# stm32h750ibk6-sig.net
KiCad netlist of a schematic drawn in Altium Designer
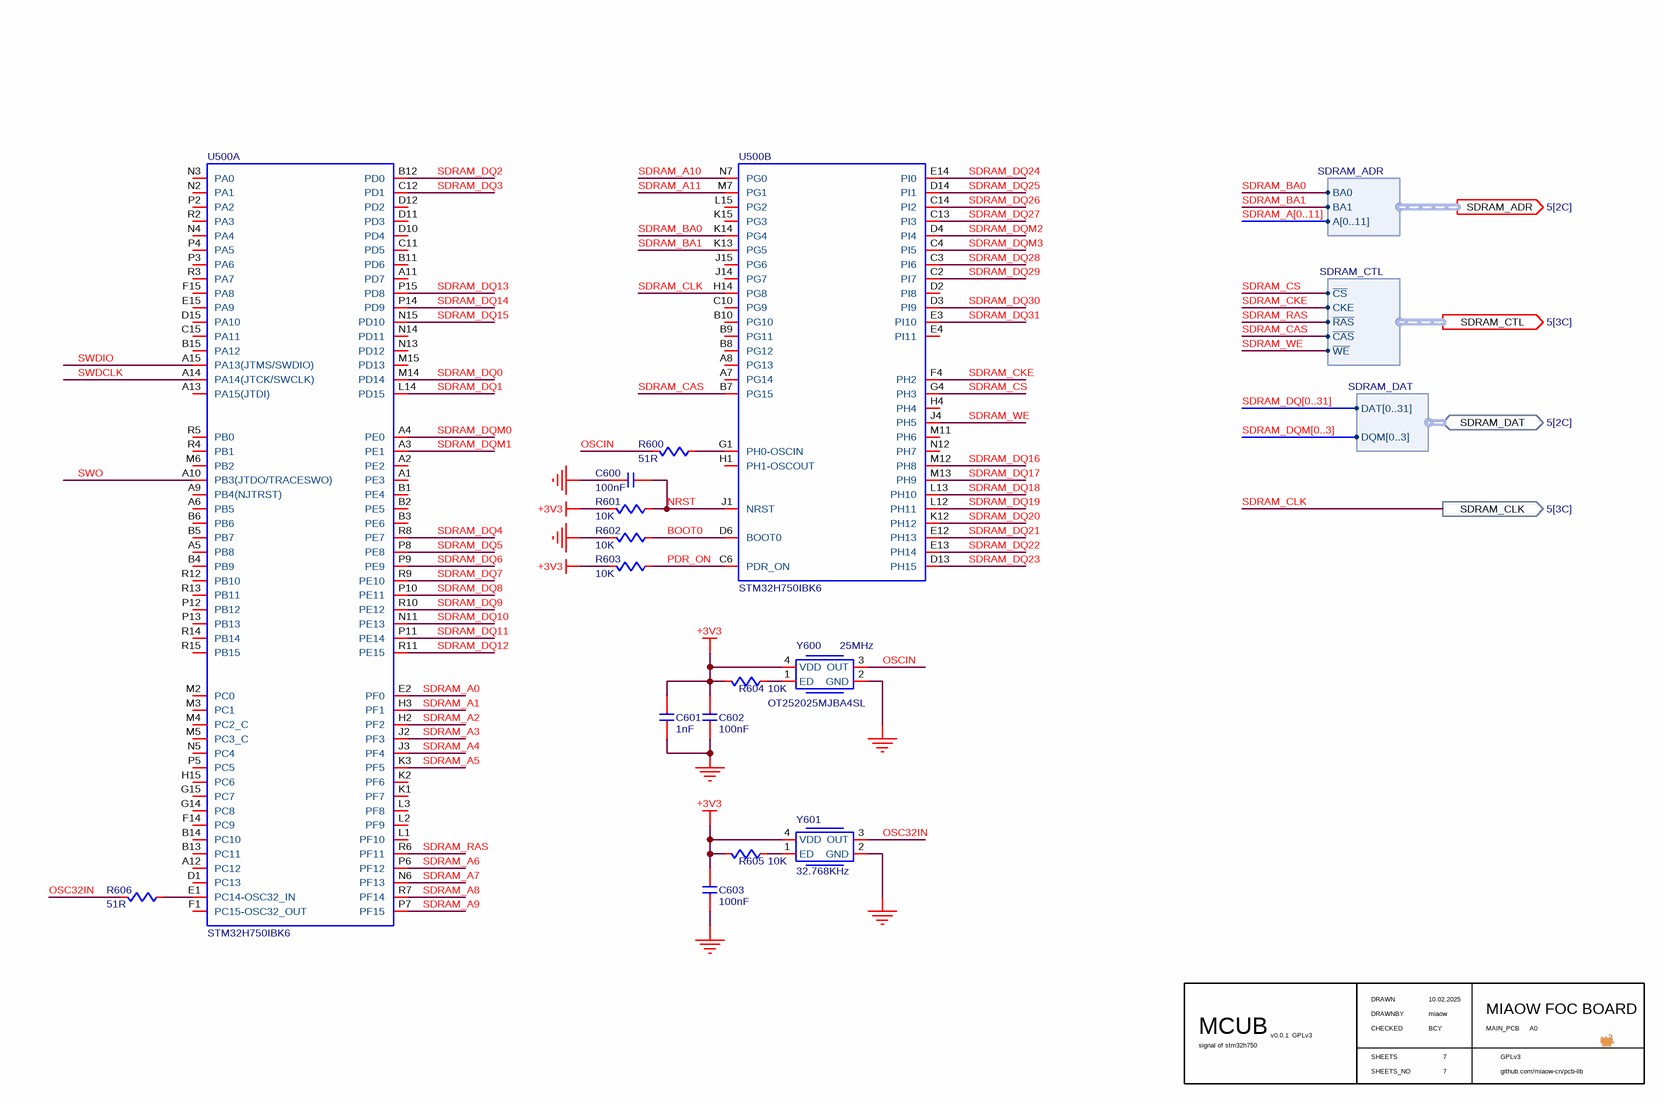
[diagram p0: stm32h750ibk6-sig.SchDoc]

(export (version "E")
  (design (tool "Eeschema 10.0.6"))
  (components
    (comp (ref "C600")
      (value "100nF")
      (footprint "mw:C0402")
      (fields (field (name "VOLTAGE") "25V") (field (name "Comment") "C-NOMO"))
      (libsource (lib "mw") (part "C-NOMO"))
    )
    (comp (ref "C601")
      (value "1nF")
      (footprint "mw:C0402")
      (fields (field (name "VOLTAGE") "25V") (field (name "Comment") "C-NOMO"))
      (libsource (lib "mw") (part "C-NOMO"))
    )
    (comp (ref "C602")
      (value "100nF")
      (footprint "mw:C0402")
      (fields (field (name "VOLTAGE") "25V") (field (name "Comment") "C-NOMO"))
      (libsource (lib "mw") (part "C-NOMO"))
    )
    (comp (ref "C603")
      (value "100nF")
      (footprint "mw:C0402")
      (fields (field (name "VOLTAGE") "25V") (field (name "Comment") "C-NOMO"))
      (libsource (lib "mw") (part "C-NOMO"))
    )
    (comp (ref "R600")
      (value "51R")
      (footprint "mw:R0402")
      (fields (field (name "Comment") "R"))
      (libsource (lib "mw") (part "R"))
    )
    (comp (ref "R601")
      (value "10K")
      (footprint "mw:R0402")
      (fields (field (name "Comment") "R"))
      (libsource (lib "mw") (part "R"))
    )
    (comp (ref "R602")
      (value "10K")
      (footprint "mw:R0402")
      (fields (field (name "Comment") "R"))
      (libsource (lib "mw") (part "R"))
    )
    (comp (ref "R603")
      (value "10K")
      (footprint "mw:R0402")
      (fields (field (name "Comment") "R"))
      (libsource (lib "mw") (part "R"))
    )
    (comp (ref "R604")
      (value "10K")
      (footprint "mw:R0402")
      (fields (field (name "Comment") "R"))
      (libsource (lib "mw") (part "R"))
    )
    (comp (ref "R605")
      (value "10K")
      (footprint "mw:R0402")
      (fields (field (name "Comment") "R"))
      (libsource (lib "mw") (part "R"))
    )
    (comp (ref "R606")
      (value "51R")
      (footprint "mw:R0402")
      (fields (field (name "Comment") "R"))
      (libsource (lib "mw") (part "R"))
    )
    (comp (ref "U500")
      (value "STM32H750IBK6")
      (footprint "mw:STM32H750IBK6")
      (libsource (lib "mw") (part "STM32H750IBK6"))
    )
    (comp (ref "Y600")
      (value "OT252025MJBA4SL")
      (footprint "mw:OT252025MJBA4SL")
      (fields (field (name "ALTIUM_VALUE") "25MHz"))
      (libsource (lib "mw") (part "OT252025MJBA4SL"))
    )
    (comp (ref "Y601")
      (value "32.768KHz")
      (footprint "mw:OK252032768KJBA4SL")
      (fields (field (name "Comment") "OK252032768KJBA4SL"))
      (libsource (lib "mw") (part "OK252032768KJBA4SL"))
    )
  )
  (nets
    (net (code "4") (name "+3V3") (class "Default")
      (node (ref "C601") (pin "1") (pinfunction "1_1") (pintype "passive"))
      (node (ref "C602") (pin "1") (pinfunction "1_1") (pintype "passive"))
      (node (ref "C603") (pin "1") (pinfunction "1_1") (pintype "passive"))
      (node (ref "R601") (pin "1") (pinfunction "1_1") (pintype "passive"))
      (node (ref "R603") (pin "1") (pinfunction "1_1") (pintype "passive"))
      (node (ref "R604") (pin "1") (pinfunction "1_1") (pintype "passive"))
      (node (ref "R605") (pin "1") (pinfunction "1_1") (pintype "passive"))
      (node (ref "Y600") (pin "4") (pinfunction "VDD_4") (pintype "passive"))
      (node (ref "Y601") (pin "4") (pinfunction "VDD_4") (pintype "passive"))
    )
    (net (code "5") (name "/BOOT0") (class "Default")
      (node (ref "R602") (pin "2") (pinfunction "2_2") (pintype "passive"))
      (node (ref "U500") (pin "D6") (pinfunction "BOOT0_D6") (pintype "passive"))
    )
    (net (code "6") (name "/NRST") (class "Default")
      (node (ref "C600") (pin "1") (pinfunction "1_1") (pintype "passive"))
      (node (ref "R601") (pin "2") (pinfunction "2_2") (pintype "passive"))
      (node (ref "U500") (pin "J1") (pinfunction "NRST_J1") (pintype "passive"))
    )
    (net (code "7") (name "/OSC32IN") (class "Default")
      (node (ref "R606") (pin "1") (pinfunction "1_1") (pintype "passive"))
      (node (ref "Y601") (pin "3") (pinfunction "OUT_3") (pintype "passive"))
    )
    (net (code "8") (name "/OSCIN") (class "Default")
      (node (ref "R600") (pin "1") (pinfunction "1_1") (pintype "passive"))
      (node (ref "Y600") (pin "3") (pinfunction "OUT_3") (pintype "passive"))
    )
    (net (code "9") (name "/PDR_ON") (class "Default")
      (node (ref "R603") (pin "2") (pinfunction "2_2") (pintype "passive"))
      (node (ref "U500") (pin "C6") (pinfunction "PDR_ON_C6") (pintype "passive"))
    )
    (net (code "10") (name "/SDRAM_A0") (class "Default")
      (node (ref "U500") (pin "E2") (pinfunction "PF0_E2") (pintype "passive"))
    )
    (net (code "11") (name "/SDRAM_A1") (class "Default")
      (node (ref "U500") (pin "H3") (pinfunction "PF1_H3") (pintype "passive"))
    )
    (net (code "12") (name "/SDRAM_A2") (class "Default")
      (node (ref "U500") (pin "H2") (pinfunction "PF2_H2") (pintype "passive"))
    )
    (net (code "13") (name "/SDRAM_A3") (class "Default")
      (node (ref "U500") (pin "J2") (pinfunction "PF3_J2") (pintype "passive"))
    )
    (net (code "14") (name "/SDRAM_A4") (class "Default")
      (node (ref "U500") (pin "J3") (pinfunction "PF4_J3") (pintype "passive"))
    )
    (net (code "15") (name "/SDRAM_A5") (class "Default")
      (node (ref "U500") (pin "K3") (pinfunction "PF5_K3") (pintype "passive"))
    )
    (net (code "16") (name "/SDRAM_A6") (class "Default")
      (node (ref "U500") (pin "P6") (pinfunction "PF12_P6") (pintype "passive"))
    )
    (net (code "17") (name "/SDRAM_A7") (class "Default")
      (node (ref "U500") (pin "N6") (pinfunction "PF13_N6") (pintype "passive"))
    )
    (net (code "18") (name "/SDRAM_A8") (class "Default")
      (node (ref "U500") (pin "R7") (pinfunction "PF14_R7") (pintype "passive"))
    )
    (net (code "19") (name "/SDRAM_A9") (class "Default")
      (node (ref "U500") (pin "P7") (pinfunction "PF15_P7") (pintype "passive"))
    )
    (net (code "20") (name "/SDRAM_A10") (class "Default")
      (node (ref "U500") (pin "N7") (pinfunction "PG0_N7") (pintype "passive"))
    )
    (net (code "21") (name "/SDRAM_A11") (class "Default")
      (node (ref "U500") (pin "M7") (pinfunction "PG1_M7") (pintype "passive"))
    )
    (net (code "23") (name "/SDRAM_BA0") (class "Default")
      (node (ref "U500") (pin "K14") (pinfunction "PG4_K14") (pintype "passive"))
    )
    (net (code "24") (name "/SDRAM_BA1") (class "Default")
      (node (ref "U500") (pin "K13") (pinfunction "PG5_K13") (pintype "passive"))
    )
    (net (code "25") (name "/SDRAM_CAS") (class "Default")
      (node (ref "U500") (pin "B7") (pinfunction "PG15_B7") (pintype "passive"))
    )
    (net (code "26") (name "/SDRAM_CKE") (class "Default")
      (node (ref "U500") (pin "F4") (pinfunction "PH2_F4") (pintype "passive"))
    )
    (net (code "27") (name "/SDRAM_CLK") (class "Default")
      (node (ref "U500") (pin "H14") (pinfunction "PG8_H14") (pintype "passive"))
    )
    (net (code "28") (name "/SDRAM_CS") (class "Default")
      (node (ref "U500") (pin "G4") (pinfunction "PH3_G4") (pintype "passive"))
    )
    (net (code "30") (name "/SDRAM_DQ0") (class "Default")
      (node (ref "U500") (pin "M14") (pinfunction "PD14_M14") (pintype "passive"))
    )
    (net (code "31") (name "/SDRAM_DQ1") (class "Default")
      (node (ref "U500") (pin "L14") (pinfunction "PD15_L14") (pintype "passive"))
    )
    (net (code "32") (name "/SDRAM_DQ2") (class "Default")
      (node (ref "U500") (pin "B12") (pinfunction "PD0_B12") (pintype "passive"))
    )
    (net (code "33") (name "/SDRAM_DQ3") (class "Default")
      (node (ref "U500") (pin "C12") (pinfunction "PD1_C12") (pintype "passive"))
    )
    (net (code "34") (name "/SDRAM_DQ4") (class "Default")
      (node (ref "U500") (pin "R8") (pinfunction "PE7_R8") (pintype "passive"))
    )
    (net (code "35") (name "/SDRAM_DQ5") (class "Default")
      (node (ref "U500") (pin "P8") (pinfunction "PE8_P8") (pintype "passive"))
    )
    (net (code "36") (name "/SDRAM_DQ6") (class "Default")
      (node (ref "U500") (pin "P9") (pinfunction "PE9_P9") (pintype "passive"))
    )
    (net (code "37") (name "/SDRAM_DQ7") (class "Default")
      (node (ref "U500") (pin "R9") (pinfunction "PE10_R9") (pintype "passive"))
    )
    (net (code "38") (name "/SDRAM_DQ8") (class "Default")
      (node (ref "U500") (pin "P10") (pinfunction "PE11_P10") (pintype "passive"))
    )
    (net (code "39") (name "/SDRAM_DQ9") (class "Default")
      (node (ref "U500") (pin "R10") (pinfunction "PE12_R10") (pintype "passive"))
    )
    (net (code "40") (name "/SDRAM_DQ10") (class "Default")
      (node (ref "U500") (pin "N11") (pinfunction "PE13_N11") (pintype "passive"))
    )
    (net (code "41") (name "/SDRAM_DQ11") (class "Default")
      (node (ref "U500") (pin "P11") (pinfunction "PE14_P11") (pintype "passive"))
    )
    (net (code "42") (name "/SDRAM_DQ12") (class "Default")
      (node (ref "U500") (pin "R11") (pinfunction "PE15_R11") (pintype "passive"))
    )
    (net (code "43") (name "/SDRAM_DQ13") (class "Default")
      (node (ref "U500") (pin "P15") (pinfunction "PD8_P15") (pintype "passive"))
    )
    (net (code "44") (name "/SDRAM_DQ14") (class "Default")
      (node (ref "U500") (pin "P14") (pinfunction "PD9_P14") (pintype "passive"))
    )
    (net (code "45") (name "/SDRAM_DQ15") (class "Default")
      (node (ref "U500") (pin "N15") (pinfunction "PD10_N15") (pintype "passive"))
    )
    (net (code "46") (name "/SDRAM_DQ16") (class "Default")
      (node (ref "U500") (pin "M12") (pinfunction "PH8_M12") (pintype "passive"))
    )
    (net (code "47") (name "/SDRAM_DQ17") (class "Default")
      (node (ref "U500") (pin "M13") (pinfunction "PH9_M13") (pintype "passive"))
    )
    (net (code "48") (name "/SDRAM_DQ18") (class "Default")
      (node (ref "U500") (pin "L13") (pinfunction "PH10_L13") (pintype "passive"))
    )
    (net (code "49") (name "/SDRAM_DQ19") (class "Default")
      (node (ref "U500") (pin "L12") (pinfunction "PH11_L12") (pintype "passive"))
    )
    (net (code "50") (name "/SDRAM_DQ20") (class "Default")
      (node (ref "U500") (pin "K12") (pinfunction "PH12_K12") (pintype "passive"))
    )
    (net (code "51") (name "/SDRAM_DQ21") (class "Default")
      (node (ref "U500") (pin "E12") (pinfunction "PH13_E12") (pintype "passive"))
    )
    (net (code "52") (name "/SDRAM_DQ22") (class "Default")
      (node (ref "U500") (pin "E13") (pinfunction "PH14_E13") (pintype "passive"))
    )
    (net (code "53") (name "/SDRAM_DQ23") (class "Default")
      (node (ref "U500") (pin "D13") (pinfunction "PH15_D13") (pintype "passive"))
    )
    (net (code "54") (name "/SDRAM_DQ24") (class "Default")
      (node (ref "U500") (pin "E14") (pinfunction "PI0_E14") (pintype "passive"))
    )
    (net (code "55") (name "/SDRAM_DQ25") (class "Default")
      (node (ref "U500") (pin "D14") (pinfunction "PI1_D14") (pintype "passive"))
    )
    (net (code "56") (name "/SDRAM_DQ26") (class "Default")
      (node (ref "U500") (pin "C14") (pinfunction "PI2_C14") (pintype "passive"))
    )
    (net (code "57") (name "/SDRAM_DQ27") (class "Default")
      (node (ref "U500") (pin "C13") (pinfunction "PI3_C13") (pintype "passive"))
    )
    (net (code "58") (name "/SDRAM_DQ28") (class "Default")
      (node (ref "U500") (pin "C3") (pinfunction "PI6_C3") (pintype "passive"))
    )
    (net (code "59") (name "/SDRAM_DQ29") (class "Default")
      (node (ref "U500") (pin "C2") (pinfunction "PI7_C2") (pintype "passive"))
    )
    (net (code "60") (name "/SDRAM_DQ30") (class "Default")
      (node (ref "U500") (pin "D3") (pinfunction "PI9_D3") (pintype "passive"))
    )
    (net (code "61") (name "/SDRAM_DQ31") (class "Default")
      (node (ref "U500") (pin "E3") (pinfunction "PI10_E3") (pintype "passive"))
    )
    (net (code "62") (name "/SDRAM_DQM0") (class "Default")
      (node (ref "U500") (pin "A4") (pinfunction "PE0_A4") (pintype "passive"))
    )
    (net (code "63") (name "/SDRAM_DQM1") (class "Default")
      (node (ref "U500") (pin "A3") (pinfunction "PE1_A3") (pintype "passive"))
    )
    (net (code "64") (name "/SDRAM_DQM2") (class "Default")
      (node (ref "U500") (pin "D4") (pinfunction "PI4_D4") (pintype "passive"))
    )
    (net (code "65") (name "/SDRAM_DQM3") (class "Default")
      (node (ref "U500") (pin "C4") (pinfunction "PI5_C4") (pintype "passive"))
    )
    (net (code "67") (name "/SDRAM_RAS") (class "Default")
      (node (ref "U500") (pin "R6") (pinfunction "PF11_R6") (pintype "passive"))
    )
    (net (code "68") (name "/SDRAM_WE") (class "Default")
      (node (ref "U500") (pin "J4") (pinfunction "PH5_J4") (pintype "passive"))
    )
    (net (code "69") (name "/SWDCLK") (class "Default")
      (node (ref "U500") (pin "A14") (pinfunction "PA14(JTCK/SWCLK)_A14") (pintype "passive"))
    )
    (net (code "70") (name "/SWDIO") (class "Default")
      (node (ref "U500") (pin "A15") (pinfunction "PA13(JTMS/SWDIO)_A15") (pintype "passive"))
    )
    (net (code "71") (name "/SWO") (class "Default")
      (node (ref "U500") (pin "A10") (pinfunction "PB3(JTDO/TRACESWO)_A10") (pintype "passive"))
    )
    (net (code "75") (name "GND") (class "Default")
      (node (ref "C600") (pin "2") (pinfunction "2_2") (pintype "passive"))
      (node (ref "C601") (pin "2") (pinfunction "2_2") (pintype "passive"))
      (node (ref "C602") (pin "2") (pinfunction "2_2") (pintype "passive"))
      (node (ref "C603") (pin "2") (pinfunction "2_2") (pintype "passive"))
      (node (ref "R602") (pin "1") (pinfunction "1_1") (pintype "passive"))
      (node (ref "Y600") (pin "2") (pinfunction "GND_2") (pintype "passive"))
      (node (ref "Y601") (pin "2") (pinfunction "GND_2") (pintype "passive"))
    )
    (net (code "76") (name "Net-(U500A-PC14-OSC32_IN)") (class "Default")
      (node (ref "R606") (pin "2") (pinfunction "2_2") (pintype "passive"))
      (node (ref "U500") (pin "E1") (pinfunction "PC14-OSC32_IN_E1") (pintype "passive"))
    )
    (net (code "77") (name "Net-(U500B-PH0-OSCIN)") (class "Default")
      (node (ref "R600") (pin "2") (pinfunction "2_2") (pintype "passive"))
      (node (ref "U500") (pin "G1") (pinfunction "PH0-OSCIN_G1") (pintype "passive"))
    )
    (net (code "78") (name "Net-(Y600-ED)") (class "Default")
      (node (ref "R604") (pin "2") (pinfunction "2_2") (pintype "passive"))
      (node (ref "Y600") (pin "1") (pinfunction "ED_1") (pintype "passive"))
    )
    (net (code "79") (name "Net-(Y601-ED)") (class "Default")
      (node (ref "R605") (pin "2") (pinfunction "2_2") (pintype "passive"))
      (node (ref "Y601") (pin "1") (pinfunction "ED_1") (pintype "passive"))
    )
    (net (code "80") (name "unconnected-(U500A-PA0-PadN3)") (class "Default")
      (node (ref "U500") (pin "N3") (pinfunction "PA0_N3") (pintype "passive"))
    )
    (net (code "81") (name "unconnected-(U500A-PA1-PadN2)") (class "Default")
      (node (ref "U500") (pin "N2") (pinfunction "PA1_N2") (pintype "passive"))
    )
    (net (code "82") (name "unconnected-(U500A-PA2-PadP2)") (class "Default")
      (node (ref "U500") (pin "P2") (pinfunction "PA2_P2") (pintype "passive"))
    )
    (net (code "83") (name "unconnected-(U500A-PA3-PadR2)") (class "Default")
      (node (ref "U500") (pin "R2") (pinfunction "PA3_R2") (pintype "passive"))
    )
    (net (code "84") (name "unconnected-(U500A-PA4-PadN4)") (class "Default")
      (node (ref "U500") (pin "N4") (pinfunction "PA4_N4") (pintype "passive"))
    )
    (net (code "85") (name "unconnected-(U500A-PA5-PadP4)") (class "Default")
      (node (ref "U500") (pin "P4") (pinfunction "PA5_P4") (pintype "passive"))
    )
    (net (code "86") (name "unconnected-(U500A-PA6-PadP3)") (class "Default")
      (node (ref "U500") (pin "P3") (pinfunction "PA6_P3") (pintype "passive"))
    )
    (net (code "87") (name "unconnected-(U500A-PA7-PadR3)") (class "Default")
      (node (ref "U500") (pin "R3") (pinfunction "PA7_R3") (pintype "passive"))
    )
    (net (code "88") (name "unconnected-(U500A-PA8-PadF15)") (class "Default")
      (node (ref "U500") (pin "F15") (pinfunction "PA8_F15") (pintype "passive"))
    )
    (net (code "89") (name "unconnected-(U500A-PA9-PadE15)") (class "Default")
      (node (ref "U500") (pin "E15") (pinfunction "PA9_E15") (pintype "passive"))
    )
    (net (code "90") (name "unconnected-(U500A-PA10-PadD15)") (class "Default")
      (node (ref "U500") (pin "D15") (pinfunction "PA10_D15") (pintype "passive"))
    )
    (net (code "91") (name "unconnected-(U500A-PA11-PadC15)") (class "Default")
      (node (ref "U500") (pin "C15") (pinfunction "PA11_C15") (pintype "passive"))
    )
    (net (code "92") (name "unconnected-(U500A-PA12-PadB15)") (class "Default")
      (node (ref "U500") (pin "B15") (pinfunction "PA12_B15") (pintype "passive"))
    )
    (net (code "93") (name "unconnected-(U500A-PA15(JTDI)-PadA13)") (class "Default")
      (node (ref "U500") (pin "A13") (pinfunction "PA15(JTDI)_A13") (pintype "passive"))
    )
    (net (code "94") (name "unconnected-(U500A-PB0-PadR5)") (class "Default")
      (node (ref "U500") (pin "R5") (pinfunction "PB0_R5") (pintype "passive"))
    )
    (net (code "95") (name "unconnected-(U500A-PB1-PadR4)") (class "Default")
      (node (ref "U500") (pin "R4") (pinfunction "PB1_R4") (pintype "passive"))
    )
    (net (code "96") (name "unconnected-(U500A-PB2-PadM6)") (class "Default")
      (node (ref "U500") (pin "M6") (pinfunction "PB2_M6") (pintype "passive"))
    )
    (net (code "97") (name "unconnected-(U500A-PB4(NJTRST)-PadA9)") (class "Default")
      (node (ref "U500") (pin "A9") (pinfunction "PB4(NJTRST)_A9") (pintype "passive"))
    )
    (net (code "98") (name "unconnected-(U500A-PB5-PadA6)") (class "Default")
      (node (ref "U500") (pin "A6") (pinfunction "PB5_A6") (pintype "passive"))
    )
    (net (code "99") (name "unconnected-(U500A-PB6-PadB6)") (class "Default")
      (node (ref "U500") (pin "B6") (pinfunction "PB6_B6") (pintype "passive"))
    )
    (net (code "100") (name "unconnected-(U500A-PB7-PadB5)") (class "Default")
      (node (ref "U500") (pin "B5") (pinfunction "PB7_B5") (pintype "passive"))
    )
    (net (code "101") (name "unconnected-(U500A-PB8-PadA5)") (class "Default")
      (node (ref "U500") (pin "A5") (pinfunction "PB8_A5") (pintype "passive"))
    )
    (net (code "102") (name "unconnected-(U500A-PB9-PadB4)") (class "Default")
      (node (ref "U500") (pin "B4") (pinfunction "PB9_B4") (pintype "passive"))
    )
    (net (code "103") (name "unconnected-(U500A-PB10-PadR12)") (class "Default")
      (node (ref "U500") (pin "R12") (pinfunction "PB10_R12") (pintype "passive"))
    )
    (net (code "104") (name "unconnected-(U500A-PB11-PadR13)") (class "Default")
      (node (ref "U500") (pin "R13") (pinfunction "PB11_R13") (pintype "passive"))
    )
    (net (code "105") (name "unconnected-(U500A-PB12-PadP12)") (class "Default")
      (node (ref "U500") (pin "P12") (pinfunction "PB12_P12") (pintype "passive"))
    )
    (net (code "106") (name "unconnected-(U500A-PB13-PadP13)") (class "Default")
      (node (ref "U500") (pin "P13") (pinfunction "PB13_P13") (pintype "passive"))
    )
    (net (code "107") (name "unconnected-(U500A-PB14-PadR14)") (class "Default")
      (node (ref "U500") (pin "R14") (pinfunction "PB14_R14") (pintype "passive"))
    )
    (net (code "108") (name "unconnected-(U500A-PB15-PadR15)") (class "Default")
      (node (ref "U500") (pin "R15") (pinfunction "PB15_R15") (pintype "passive"))
    )
    (net (code "109") (name "unconnected-(U500A-PC0-PadM2)") (class "Default")
      (node (ref "U500") (pin "M2") (pinfunction "PC0_M2") (pintype "passive"))
    )
    (net (code "110") (name "unconnected-(U500A-PC1-PadM3)") (class "Default")
      (node (ref "U500") (pin "M3") (pinfunction "PC1_M3") (pintype "passive"))
    )
    (net (code "111") (name "unconnected-(U500A-PC2_C-PadM4)") (class "Default")
      (node (ref "U500") (pin "M4") (pinfunction "PC2_C_M4") (pintype "passive"))
    )
    (net (code "112") (name "unconnected-(U500A-PC3_C-PadM5)") (class "Default")
      (node (ref "U500") (pin "M5") (pinfunction "PC3_C_M5") (pintype "passive"))
    )
    (net (code "113") (name "unconnected-(U500A-PC4-PadN5)") (class "Default")
      (node (ref "U500") (pin "N5") (pinfunction "PC4_N5") (pintype "passive"))
    )
    (net (code "114") (name "unconnected-(U500A-PC5-PadP5)") (class "Default")
      (node (ref "U500") (pin "P5") (pinfunction "PC5_P5") (pintype "passive"))
    )
    (net (code "115") (name "unconnected-(U500A-PC6-PadH15)") (class "Default")
      (node (ref "U500") (pin "H15") (pinfunction "PC6_H15") (pintype "passive"))
    )
    (net (code "116") (name "unconnected-(U500A-PC7-PadG15)") (class "Default")
      (node (ref "U500") (pin "G15") (pinfunction "PC7_G15") (pintype "passive"))
    )
    (net (code "117") (name "unconnected-(U500A-PC8-PadG14)") (class "Default")
      (node (ref "U500") (pin "G14") (pinfunction "PC8_G14") (pintype "passive"))
    )
    (net (code "118") (name "unconnected-(U500A-PC9-PadF14)") (class "Default")
      (node (ref "U500") (pin "F14") (pinfunction "PC9_F14") (pintype "passive"))
    )
    (net (code "119") (name "unconnected-(U500A-PC10-PadB14)") (class "Default")
      (node (ref "U500") (pin "B14") (pinfunction "PC10_B14") (pintype "passive"))
    )
    (net (code "120") (name "unconnected-(U500A-PC11-PadB13)") (class "Default")
      (node (ref "U500") (pin "B13") (pinfunction "PC11_B13") (pintype "passive"))
    )
    (net (code "121") (name "unconnected-(U500A-PC12-PadA12)") (class "Default")
      (node (ref "U500") (pin "A12") (pinfunction "PC12_A12") (pintype "passive"))
    )
    (net (code "122") (name "unconnected-(U500A-PC13-PadD1)") (class "Default")
      (node (ref "U500") (pin "D1") (pinfunction "PC13_D1") (pintype "passive"))
    )
    (net (code "123") (name "unconnected-(U500A-PC15-OSC32_OUT-PadF1)") (class "Default")
      (node (ref "U500") (pin "F1") (pinfunction "PC15-OSC32_OUT_F1") (pintype "passive"))
    )
    (net (code "124") (name "unconnected-(U500A-PD2-PadD12)") (class "Default")
      (node (ref "U500") (pin "D12") (pinfunction "PD2_D12") (pintype "passive"))
    )
    (net (code "125") (name "unconnected-(U500A-PD3-PadD11)") (class "Default")
      (node (ref "U500") (pin "D11") (pinfunction "PD3_D11") (pintype "passive"))
    )
    (net (code "126") (name "unconnected-(U500A-PD4-PadD10)") (class "Default")
      (node (ref "U500") (pin "D10") (pinfunction "PD4_D10") (pintype "passive"))
    )
    (net (code "127") (name "unconnected-(U500A-PD5-PadC11)") (class "Default")
      (node (ref "U500") (pin "C11") (pinfunction "PD5_C11") (pintype "passive"))
    )
    (net (code "128") (name "unconnected-(U500A-PD6-PadB11)") (class "Default")
      (node (ref "U500") (pin "B11") (pinfunction "PD6_B11") (pintype "passive"))
    )
    (net (code "129") (name "unconnected-(U500A-PD7-PadA11)") (class "Default")
      (node (ref "U500") (pin "A11") (pinfunction "PD7_A11") (pintype "passive"))
    )
    (net (code "130") (name "unconnected-(U500A-PD11-PadN14)") (class "Default")
      (node (ref "U500") (pin "N14") (pinfunction "PD11_N14") (pintype "passive"))
    )
    (net (code "131") (name "unconnected-(U500A-PD12-PadN13)") (class "Default")
      (node (ref "U500") (pin "N13") (pinfunction "PD12_N13") (pintype "passive"))
    )
    (net (code "132") (name "unconnected-(U500A-PD13-PadM15)") (class "Default")
      (node (ref "U500") (pin "M15") (pinfunction "PD13_M15") (pintype "passive"))
    )
    (net (code "133") (name "unconnected-(U500A-PE2-PadA2)") (class "Default")
      (node (ref "U500") (pin "A2") (pinfunction "PE2_A2") (pintype "passive"))
    )
    (net (code "134") (name "unconnected-(U500A-PE3-PadA1)") (class "Default")
      (node (ref "U500") (pin "A1") (pinfunction "PE3_A1") (pintype "passive"))
    )
    (net (code "135") (name "unconnected-(U500A-PE4-PadB1)") (class "Default")
      (node (ref "U500") (pin "B1") (pinfunction "PE4_B1") (pintype "passive"))
    )
    (net (code "136") (name "unconnected-(U500A-PE5-PadB2)") (class "Default")
      (node (ref "U500") (pin "B2") (pinfunction "PE5_B2") (pintype "passive"))
    )
    (net (code "137") (name "unconnected-(U500A-PE6-PadB3)") (class "Default")
      (node (ref "U500") (pin "B3") (pinfunction "PE6_B3") (pintype "passive"))
    )
    (net (code "138") (name "unconnected-(U500A-PF6-PadK2)") (class "Default")
      (node (ref "U500") (pin "K2") (pinfunction "PF6_K2") (pintype "passive"))
    )
    (net (code "139") (name "unconnected-(U500A-PF7-PadK1)") (class "Default")
      (node (ref "U500") (pin "K1") (pinfunction "PF7_K1") (pintype "passive"))
    )
    (net (code "140") (name "unconnected-(U500A-PF8-PadL3)") (class "Default")
      (node (ref "U500") (pin "L3") (pinfunction "PF8_L3") (pintype "passive"))
    )
    (net (code "141") (name "unconnected-(U500A-PF9-PadL2)") (class "Default")
      (node (ref "U500") (pin "L2") (pinfunction "PF9_L2") (pintype "passive"))
    )
    (net (code "142") (name "unconnected-(U500A-PF10-PadL1)") (class "Default")
      (node (ref "U500") (pin "L1") (pinfunction "PF10_L1") (pintype "passive"))
    )
    (net (code "143") (name "unconnected-(U500B-PG2-PadL15)") (class "Default")
      (node (ref "U500") (pin "L15") (pinfunction "PG2_L15") (pintype "passive"))
    )
    (net (code "144") (name "unconnected-(U500B-PG3-PadK15)") (class "Default")
      (node (ref "U500") (pin "K15") (pinfunction "PG3_K15") (pintype "passive"))
    )
    (net (code "145") (name "unconnected-(U500B-PG6-PadJ15)") (class "Default")
      (node (ref "U500") (pin "J15") (pinfunction "PG6_J15") (pintype "passive"))
    )
    (net (code "146") (name "unconnected-(U500B-PG7-PadJ14)") (class "Default")
      (node (ref "U500") (pin "J14") (pinfunction "PG7_J14") (pintype "passive"))
    )
    (net (code "147") (name "unconnected-(U500B-PG9-PadC10)") (class "Default")
      (node (ref "U500") (pin "C10") (pinfunction "PG9_C10") (pintype "passive"))
    )
    (net (code "148") (name "unconnected-(U500B-PG10-PadB10)") (class "Default")
      (node (ref "U500") (pin "B10") (pinfunction "PG10_B10") (pintype "passive"))
    )
    (net (code "149") (name "unconnected-(U500B-PG11-PadB9)") (class "Default")
      (node (ref "U500") (pin "B9") (pinfunction "PG11_B9") (pintype "passive"))
    )
    (net (code "150") (name "unconnected-(U500B-PG12-PadB8)") (class "Default")
      (node (ref "U500") (pin "B8") (pinfunction "PG12_B8") (pintype "passive"))
    )
    (net (code "151") (name "unconnected-(U500B-PG13-PadA8)") (class "Default")
      (node (ref "U500") (pin "A8") (pinfunction "PG13_A8") (pintype "passive"))
    )
    (net (code "152") (name "unconnected-(U500B-PG14-PadA7)") (class "Default")
      (node (ref "U500") (pin "A7") (pinfunction "PG14_A7") (pintype "passive"))
    )
    (net (code "153") (name "unconnected-(U500B-PH1-OSCOUT-PadH1)") (class "Default")
      (node (ref "U500") (pin "H1") (pinfunction "PH1-OSCOUT_H1") (pintype "passive"))
    )
    (net (code "154") (name "unconnected-(U500B-PH4-PadH4)") (class "Default")
      (node (ref "U500") (pin "H4") (pinfunction "PH4_H4") (pintype "passive"))
    )
    (net (code "155") (name "unconnected-(U500B-PH6-PadM11)") (class "Default")
      (node (ref "U500") (pin "M11") (pinfunction "PH6_M11") (pintype "passive"))
    )
    (net (code "156") (name "unconnected-(U500B-PH7-PadN12)") (class "Default")
      (node (ref "U500") (pin "N12") (pinfunction "PH7_N12") (pintype "passive"))
    )
    (net (code "157") (name "unconnected-(U500B-PI8-PadD2)") (class "Default")
      (node (ref "U500") (pin "D2") (pinfunction "PI8_D2") (pintype "passive"))
    )
    (net (code "158") (name "unconnected-(U500B-PI11-PadE4)") (class "Default")
      (node (ref "U500") (pin "E4") (pinfunction "PI11_E4") (pintype "passive"))
    )
  )
)
